# USB_Zigbee_V1_0.net
KiCad netlist of a schematic drawn in EAGLE
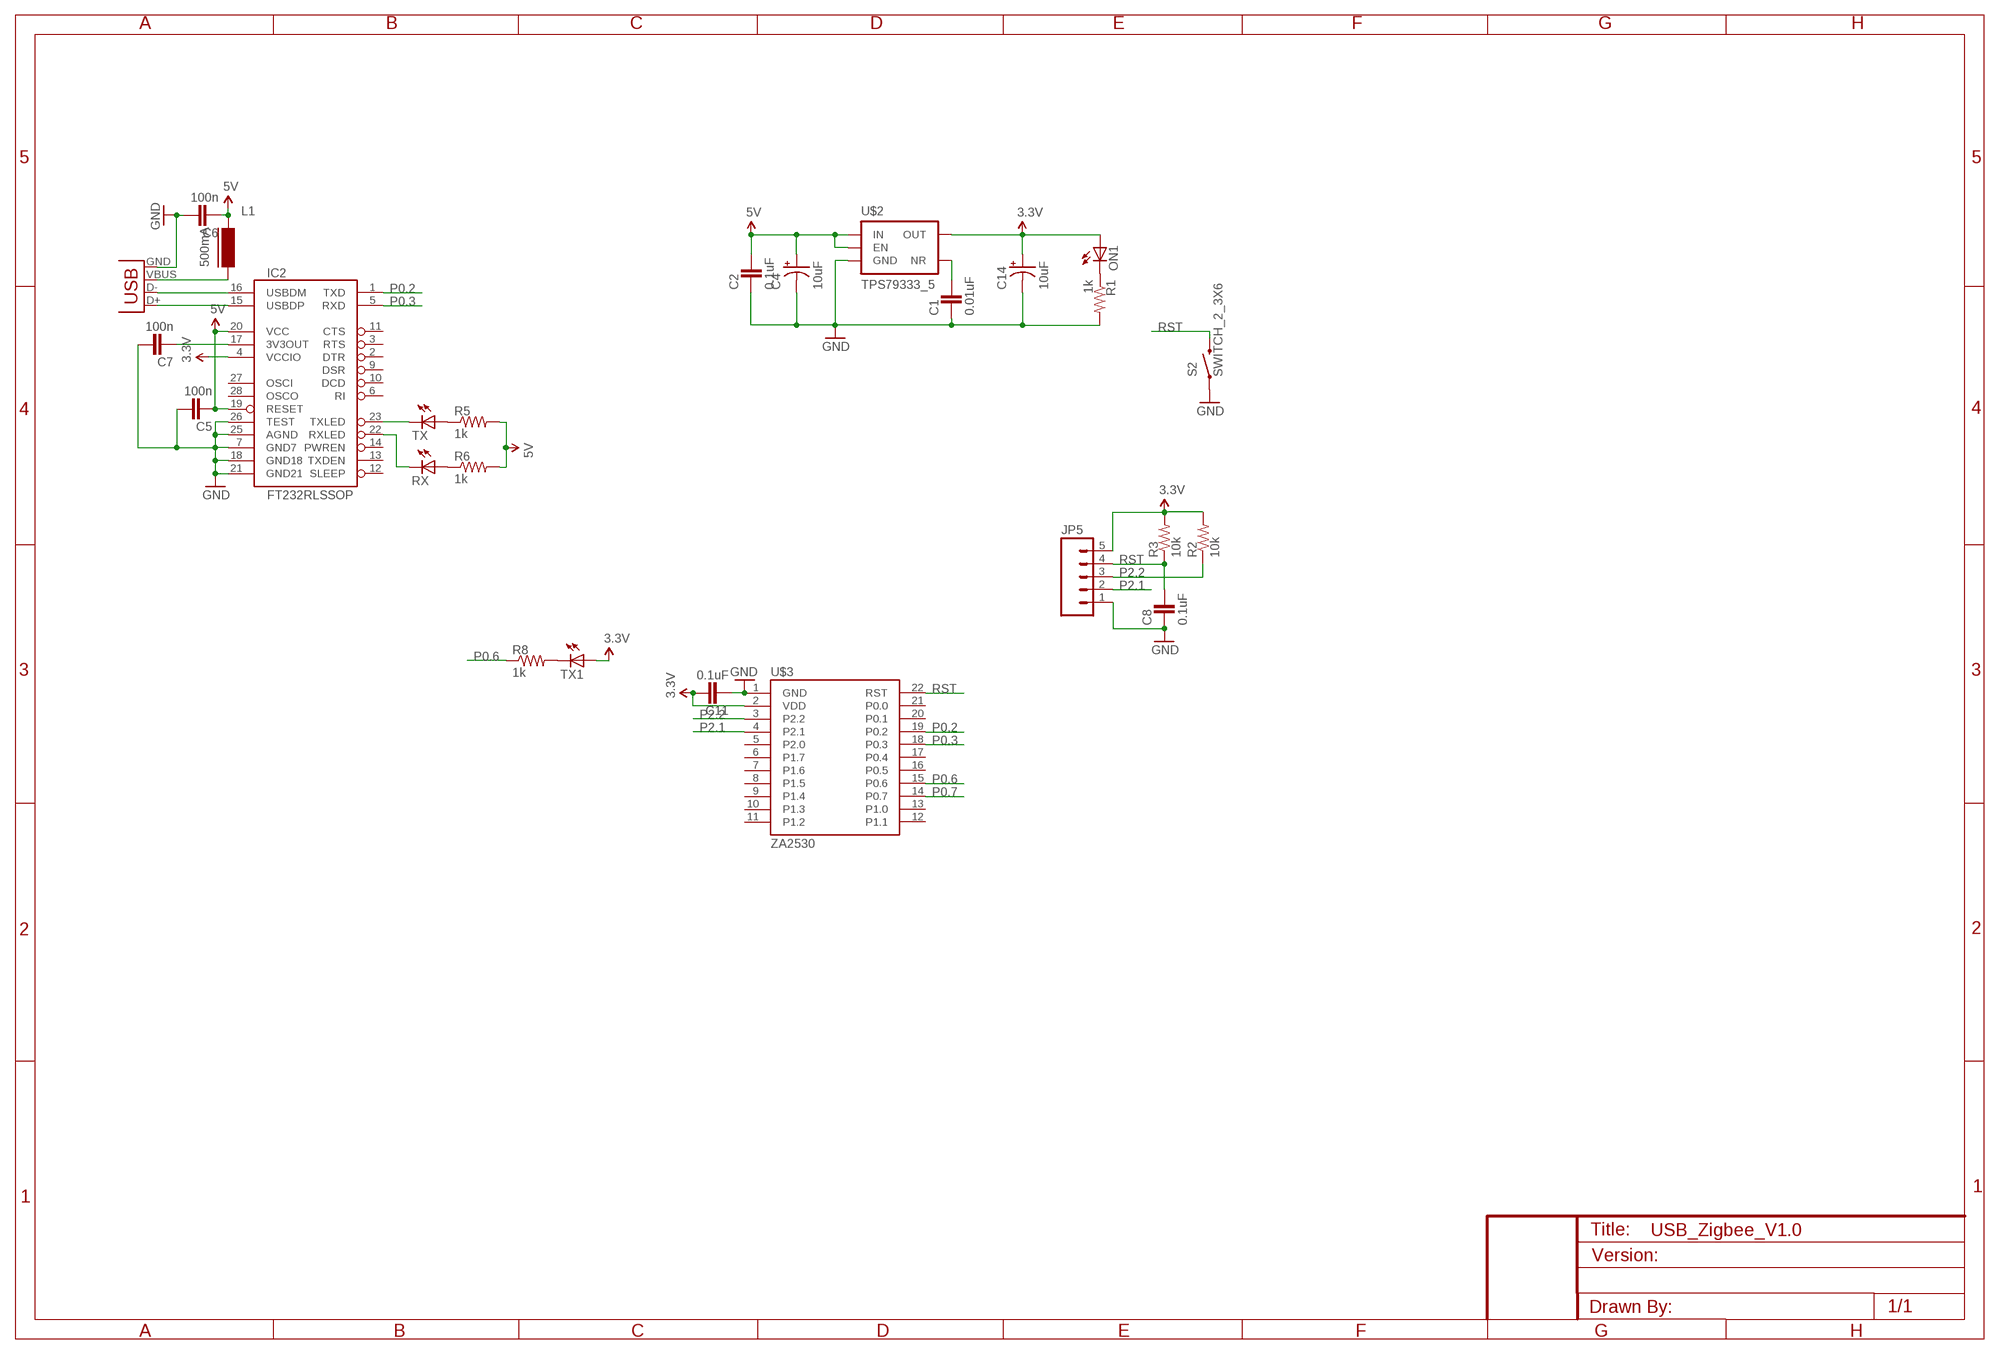
[diagram p0: schematic, sheet 1]

(export (version "E")
  (design (tool "Eeschema 10.0.6"))
  (components
    (comp (ref "C1")
      (value "0.01uF")
      (footprint "eagle-import:0603-CAP")
      (libsource (lib "eagle-import") (part "CAP0603"))
    )
    (comp (ref "C2")
      (value "0.1uF")
      (footprint "eagle-import:0603-CAP")
      (libsource (lib "eagle-import") (part "CAP0603"))
    )
    (comp (ref "C4")
      (value "10uF")
      (footprint "eagle-import:EIA3216")
      (libsource (lib "eagle-import") (part "CAP_POL1206"))
    )
    (comp (ref "C5")
      (value "100n")
      (footprint "eagle-import:0603-CAP")
      (libsource (lib "eagle-import") (part "CAP0603"))
    )
    (comp (ref "C6")
      (value "100n")
      (footprint "eagle-import:0603-CAP")
      (libsource (lib "eagle-import") (part "CAP0603"))
    )
    (comp (ref "C7")
      (value "100n")
      (footprint "eagle-import:0603-CAP")
      (libsource (lib "eagle-import") (part "CAP0603"))
    )
    (comp (ref "C8")
      (value "0.1uF")
      (footprint "eagle-import:0603-CAP")
      (libsource (lib "eagle-import") (part "CAP0603"))
    )
    (comp (ref "C11")
      (value "0.1uF")
      (footprint "eagle-import:0603-CAP")
      (libsource (lib "eagle-import") (part "CAP0603"))
    )
    (comp (ref "C14")
      (value "10uF")
      (footprint "eagle-import:EIA3216")
      (libsource (lib "eagle-import") (part "CAP_POL1206"))
    )
    (comp (ref "IC2")
      (value "FT232RLSSOP")
      (footprint "eagle-import:SSOP28DB")
      (libsource (lib "eagle-import") (part "FT232RLSSOP"))
    )
    (comp (ref "JP5")
      (value "M05PTH")
      (footprint "eagle-import:1X05")
      (libsource (lib "eagle-import") (part "M05PTH"))
    )
    (comp (ref "L1")
      (value "500mA")
      (footprint "eagle-import:FB805")
      (libsource (lib "eagle-import") (part "FERRITE-0805"))
    )
    (comp (ref "ON1")
      (value "LED0603")
      (footprint "eagle-import:LED-0603")
      (libsource (lib "eagle-import") (part "LED0603"))
    )
    (comp (ref "R1")
      (value "1k")
      (footprint "eagle-import:0603-RES")
      (libsource (lib "eagle-import") (part "RESISTOR0603-RES"))
    )
    (comp (ref "R2")
      (value "10k")
      (footprint "eagle-import:0603-RES")
      (libsource (lib "eagle-import") (part "RESISTOR0603-RES"))
    )
    (comp (ref "R3")
      (value "10k")
      (footprint "eagle-import:0603-RES")
      (libsource (lib "eagle-import") (part "RESISTOR0603-RES"))
    )
    (comp (ref "R5")
      (value "1k")
      (footprint "eagle-import:0603-RES")
      (libsource (lib "eagle-import") (part "RESISTOR0603-RES"))
    )
    (comp (ref "R6")
      (value "1k")
      (footprint "eagle-import:0603-RES")
      (libsource (lib "eagle-import") (part "RESISTOR0603-RES"))
    )
    (comp (ref "R8")
      (value "1k")
      (footprint "eagle-import:0603-RES")
      (libsource (lib "eagle-import") (part "RESISTOR0603-RES"))
    )
    (comp (ref "RX")
      (value "LED0603")
      (footprint "eagle-import:LED-0603")
      (libsource (lib "eagle-import") (part "LED0603"))
    )
    (comp (ref "S2")
      (value "SWITCH_2_3X6")
      (footprint "eagle-import:TACTILE-SWITCH-1101NE")
      (libsource (lib "eagle-import") (part "SWITCH_2_3X6"))
    )
    (comp (ref "TX")
      (value "LED0603")
      (footprint "eagle-import:LED-0603")
      (libsource (lib "eagle-import") (part "LED0603"))
    )
    (comp (ref "TX1")
      (value "LED0603")
      (footprint "eagle-import:LED-0603")
      (libsource (lib "eagle-import") (part "LED0603"))
    )
    (comp (ref "U$2")
      (value "TPS79333_5")
      (footprint "eagle-import:SOT23-5")
      (libsource (lib "eagle-import") (part "TPS79333_5"))
    )
    (comp (ref "U$3")
      (value "ZA2530")
      (footprint "eagle-import:ZA2530")
      (libsource (lib "eagle-import") (part "ZA2530"))
    )
    (comp (ref "X1")
      (value "USB_4-A-H_2")
      (footprint "eagle-import:USB-A-H_2")
      (libsource (lib "eagle-import") (part "USB_4-A-H_2"))
    )
  )
  (nets
    (net (code "1") (name "/P0.2") (class "Default")
      (node (ref "IC2") (pin "1") (pinfunction "TXD_1") (pintype "output"))
      (node (ref "U$3") (pin "19") (pinfunction "P0.2_19") (pintype "bidirectional"))
    )
    (net (code "2") (name "/P0.3") (class "Default")
      (node (ref "IC2") (pin "5") (pinfunction "RXD_5") (pintype "input"))
      (node (ref "U$3") (pin "18") (pinfunction "P0.3_18") (pintype "bidirectional"))
    )
    (net (code "3") (name "/P0.6") (class "Default")
      (node (ref "R8") (pin "1") (pinfunction "1_1") (pintype "passive"))
      (node (ref "U$3") (pin "15") (pinfunction "P0.6_15") (pintype "bidirectional"))
    )
    (net (code "4") (name "/P0.7") (class "Default")
      (node (ref "U$3") (pin "14") (pinfunction "P0.7_14") (pintype "bidirectional"))
    )
    (net (code "5") (name "/P2.1") (class "Default")
      (node (ref "JP5") (pin "2") (pinfunction "2_2") (pintype "passive"))
      (node (ref "U$3") (pin "4") (pinfunction "P2.1_4") (pintype "bidirectional"))
    )
    (net (code "6") (name "/P2.2") (class "Default")
      (node (ref "JP5") (pin "3") (pinfunction "3_3") (pintype "passive"))
      (node (ref "R2") (pin "1") (pinfunction "1_1") (pintype "passive"))
      (node (ref "U$3") (pin "3") (pinfunction "P2.2_3") (pintype "bidirectional"))
    )
    (net (code "7") (name "/RST") (class "Default")
      (node (ref "C8") (pin "1") (pinfunction "1_1") (pintype "passive"))
      (node (ref "JP5") (pin "4") (pinfunction "4_4") (pintype "passive"))
      (node (ref "R3") (pin "1") (pinfunction "1_1") (pintype "passive"))
      (node (ref "S2") (pin "P$2") (pinfunction "2_P$2") (pintype "passive"))
      (node (ref "U$3") (pin "22") (pinfunction "RST_22") (pintype "bidirectional"))
    )
    (net (code "8") (name "3.3V") (class "Default")
      (node (ref "C11") (pin "1") (pinfunction "1_1") (pintype "passive"))
      (node (ref "C14") (pin "A") (pinfunction "+_A") (pintype "passive"))
      (node (ref "IC2") (pin "4") (pinfunction "VCCIO_4") (pintype "power_in"))
      (node (ref "JP5") (pin "5") (pinfunction "5_5") (pintype "passive"))
      (node (ref "ON1") (pin "A") (pinfunction "A_A") (pintype "passive"))
      (node (ref "R2") (pin "2") (pinfunction "2_2") (pintype "passive"))
      (node (ref "R3") (pin "2") (pinfunction "2_2") (pintype "passive"))
      (node (ref "TX1") (pin "A") (pinfunction "A_A") (pintype "passive"))
      (node (ref "U$2") (pin "5") (pinfunction "OUT_5") (pintype "power_in"))
      (node (ref "U$3") (pin "2") (pinfunction "VDD_2") (pintype "bidirectional"))
    )
    (net (code "9") (name "5V") (class "Default")
      (node (ref "C2") (pin "1") (pinfunction "1_1") (pintype "passive"))
      (node (ref "C4") (pin "A") (pinfunction "+_A") (pintype "passive"))
      (node (ref "C5") (pin "2") (pinfunction "2_2") (pintype "passive"))
      (node (ref "C6") (pin "2") (pinfunction "2_2") (pintype "passive"))
      (node (ref "IC2") (pin "19") (pinfunction "RESET_19") (pintype "input"))
      (node (ref "IC2") (pin "20") (pinfunction "VCC_20") (pintype "power_in"))
      (node (ref "L1") (pin "1") (pinfunction "1_1") (pintype "passive"))
      (node (ref "R5") (pin "2") (pinfunction "2_2") (pintype "passive"))
      (node (ref "R6") (pin "2") (pinfunction "2_2") (pintype "passive"))
      (node (ref "U$2") (pin "1") (pinfunction "IN_1") (pintype "power_in"))
      (node (ref "U$2") (pin "3") (pinfunction "EN_3") (pintype "bidirectional"))
    )
    (net (code "10") (name "GND") (class "Default")
      (node (ref "C1") (pin "2") (pinfunction "2_2") (pintype "passive"))
      (node (ref "C11") (pin "2") (pinfunction "2_2") (pintype "passive"))
      (node (ref "C14") (pin "C") (pinfunction "-_C") (pintype "passive"))
      (node (ref "C2") (pin "2") (pinfunction "2_2") (pintype "passive"))
      (node (ref "C4") (pin "C") (pinfunction "-_C") (pintype "passive"))
      (node (ref "C5") (pin "1") (pinfunction "1_1") (pintype "passive"))
      (node (ref "C6") (pin "1") (pinfunction "1_1") (pintype "passive"))
      (node (ref "C7") (pin "1") (pinfunction "1_1") (pintype "passive"))
      (node (ref "C8") (pin "2") (pinfunction "2_2") (pintype "passive"))
      (node (ref "IC2") (pin "18") (pinfunction "GND18_18") (pintype "power_in"))
      (node (ref "IC2") (pin "21") (pinfunction "GND21_21") (pintype "power_in"))
      (node (ref "IC2") (pin "25") (pinfunction "AGND_25") (pintype "power_in"))
      (node (ref "IC2") (pin "26") (pinfunction "TEST_26") (pintype "input"))
      (node (ref "IC2") (pin "7") (pinfunction "GND7_7") (pintype "power_in"))
      (node (ref "JP5") (pin "1") (pinfunction "1_1") (pintype "passive"))
      (node (ref "R1") (pin "2") (pinfunction "2_2") (pintype "passive"))
      (node (ref "S2") (pin "P$1") (pinfunction "1_P$1") (pintype "passive"))
      (node (ref "U$2") (pin "2") (pinfunction "GND_2") (pintype "power_in"))
      (node (ref "U$3") (pin "1") (pinfunction "GND_1") (pintype "bidirectional"))
      (node (ref "X1") (pin "GND") (pinfunction "GND_GND") (pintype "bidirectional"))
    )
    (net (code "11") (name "Net-(IC2-3V3OUT)") (class "Default")
      (node (ref "C7") (pin "2") (pinfunction "2_2") (pintype "passive"))
      (node (ref "IC2") (pin "17") (pinfunction "3V3OUT_17") (pintype "output"))
    )
    (net (code "12") (name "Net-(IC2-RXLED)") (class "Default")
      (node (ref "IC2") (pin "22") (pinfunction "RXLED_22") (pintype "input"))
      (node (ref "RX") (pin "C") (pinfunction "C_C") (pintype "passive"))
    )
    (net (code "13") (name "Net-(IC2-TXLED)") (class "Default")
      (node (ref "IC2") (pin "23") (pinfunction "TXLED_23") (pintype "input"))
      (node (ref "TX") (pin "C") (pinfunction "C_C") (pintype "passive"))
    )
    (net (code "14") (name "Net-(IC2-USBDM)") (class "Default")
      (node (ref "IC2") (pin "16") (pinfunction "USBDM_16") (pintype "bidirectional"))
      (node (ref "X1") (pin "D-") (pinfunction "D-_D-") (pintype "bidirectional"))
    )
    (net (code "15") (name "Net-(IC2-USBDP)") (class "Default")
      (node (ref "IC2") (pin "15") (pinfunction "USBDP_15") (pintype "bidirectional"))
      (node (ref "X1") (pin "D+") (pinfunction "D+_D+") (pintype "bidirectional"))
    )
    (net (code "16") (name "Net-(L1-Pad2)") (class "Default")
      (node (ref "L1") (pin "2") (pinfunction "2_2") (pintype "passive"))
      (node (ref "X1") (pin "VBUS") (pinfunction "VBUS_VBUS") (pintype "bidirectional"))
    )
    (net (code "17") (name "Net-(ON1-PadC)") (class "Default")
      (node (ref "ON1") (pin "C") (pinfunction "C_C") (pintype "passive"))
      (node (ref "R1") (pin "1") (pinfunction "1_1") (pintype "passive"))
    )
    (net (code "18") (name "Net-(R5-Pad1)") (class "Default")
      (node (ref "R5") (pin "1") (pinfunction "1_1") (pintype "passive"))
      (node (ref "TX") (pin "A") (pinfunction "A_A") (pintype "passive"))
    )
    (net (code "19") (name "Net-(R6-Pad1)") (class "Default")
      (node (ref "R6") (pin "1") (pinfunction "1_1") (pintype "passive"))
      (node (ref "RX") (pin "A") (pinfunction "A_A") (pintype "passive"))
    )
    (net (code "20") (name "Net-(R8-Pad2)") (class "Default")
      (node (ref "R8") (pin "2") (pinfunction "2_2") (pintype "passive"))
      (node (ref "TX1") (pin "C") (pinfunction "C_C") (pintype "passive"))
    )
    (net (code "21") (name "Net-(U$2-NR)") (class "Default")
      (node (ref "C1") (pin "1") (pinfunction "1_1") (pintype "passive"))
      (node (ref "U$2") (pin "4") (pinfunction "NR_4") (pintype "bidirectional"))
    )
    (net (code "22") (name "unconnected-(IC2-CTS-Pad11)") (class "Default")
      (node (ref "IC2") (pin "11") (pinfunction "CTS_11") (pintype "input"))
    )
    (net (code "23") (name "unconnected-(IC2-DCD-Pad10)") (class "Default")
      (node (ref "IC2") (pin "10") (pinfunction "DCD_10") (pintype "input"))
    )
    (net (code "24") (name "unconnected-(IC2-DSR-Pad9)") (class "Default")
      (node (ref "IC2") (pin "9") (pinfunction "DSR_9") (pintype "input"))
    )
    (net (code "25") (name "unconnected-(IC2-DTR-Pad2)") (class "Default")
      (node (ref "IC2") (pin "2") (pinfunction "DTR_2") (pintype "output"))
    )
    (net (code "26") (name "unconnected-(IC2-OSCI-Pad27)") (class "Default")
      (node (ref "IC2") (pin "27") (pinfunction "OSCI_27") (pintype "input"))
    )
    (net (code "27") (name "unconnected-(IC2-OSCO-Pad28)") (class "Default")
      (node (ref "IC2") (pin "28") (pinfunction "OSCO_28") (pintype "output"))
    )
    (net (code "28") (name "unconnected-(IC2-PWREN-Pad14)") (class "Default")
      (node (ref "IC2") (pin "14") (pinfunction "PWREN_14") (pintype "input"))
    )
    (net (code "29") (name "unconnected-(IC2-RI-Pad6)") (class "Default")
      (node (ref "IC2") (pin "6") (pinfunction "RI_6") (pintype "input"))
    )
    (net (code "30") (name "unconnected-(IC2-RTS-Pad3)") (class "Default")
      (node (ref "IC2") (pin "3") (pinfunction "RTS_3") (pintype "output"))
    )
    (net (code "31") (name "unconnected-(IC2-SLEEP-Pad12)") (class "Default")
      (node (ref "IC2") (pin "12") (pinfunction "SLEEP_12") (pintype "input"))
    )
    (net (code "32") (name "unconnected-(IC2-TXDEN-Pad13)") (class "Default")
      (node (ref "IC2") (pin "13") (pinfunction "TXDEN_13") (pintype "input"))
    )
    (net (code "33") (name "unconnected-(U$3-P0.0-Pad21)") (class "Default")
      (node (ref "U$3") (pin "21") (pinfunction "P0.0_21") (pintype "bidirectional"))
    )
    (net (code "34") (name "unconnected-(U$3-P0.1-Pad20)") (class "Default")
      (node (ref "U$3") (pin "20") (pinfunction "P0.1_20") (pintype "bidirectional"))
    )
    (net (code "35") (name "unconnected-(U$3-P0.4-Pad17)") (class "Default")
      (node (ref "U$3") (pin "17") (pinfunction "P0.4_17") (pintype "bidirectional"))
    )
    (net (code "36") (name "unconnected-(U$3-P0.5-Pad16)") (class "Default")
      (node (ref "U$3") (pin "16") (pinfunction "P0.5_16") (pintype "bidirectional"))
    )
    (net (code "37") (name "unconnected-(U$3-P1.0-Pad13)") (class "Default")
      (node (ref "U$3") (pin "13") (pinfunction "P1.0_13") (pintype "bidirectional"))
    )
    (net (code "38") (name "unconnected-(U$3-P1.1-Pad12)") (class "Default")
      (node (ref "U$3") (pin "12") (pinfunction "P1.1_12") (pintype "bidirectional"))
    )
    (net (code "39") (name "unconnected-(U$3-P1.2-Pad11)") (class "Default")
      (node (ref "U$3") (pin "11") (pinfunction "P1.2_11") (pintype "bidirectional"))
    )
    (net (code "40") (name "unconnected-(U$3-P1.3-Pad10)") (class "Default")
      (node (ref "U$3") (pin "10") (pinfunction "P1.3_10") (pintype "bidirectional"))
    )
    (net (code "41") (name "unconnected-(U$3-P1.4-Pad9)") (class "Default")
      (node (ref "U$3") (pin "9") (pinfunction "P1.4_9") (pintype "bidirectional"))
    )
    (net (code "42") (name "unconnected-(U$3-P1.5-Pad8)") (class "Default")
      (node (ref "U$3") (pin "8") (pinfunction "P1.5_8") (pintype "bidirectional"))
    )
    (net (code "43") (name "unconnected-(U$3-P1.6-Pad7)") (class "Default")
      (node (ref "U$3") (pin "7") (pinfunction "P1.6_7") (pintype "bidirectional"))
    )
    (net (code "44") (name "unconnected-(U$3-P1.7-Pad6)") (class "Default")
      (node (ref "U$3") (pin "6") (pinfunction "P1.7_6") (pintype "bidirectional"))
    )
    (net (code "45") (name "unconnected-(U$3-P2.0-Pad5)") (class "Default")
      (node (ref "U$3") (pin "5") (pinfunction "P2.0_5") (pintype "bidirectional"))
    )
  )
)
